# modemIO_v1.net
KiCad netlist of a schematic drawn in EAGLE
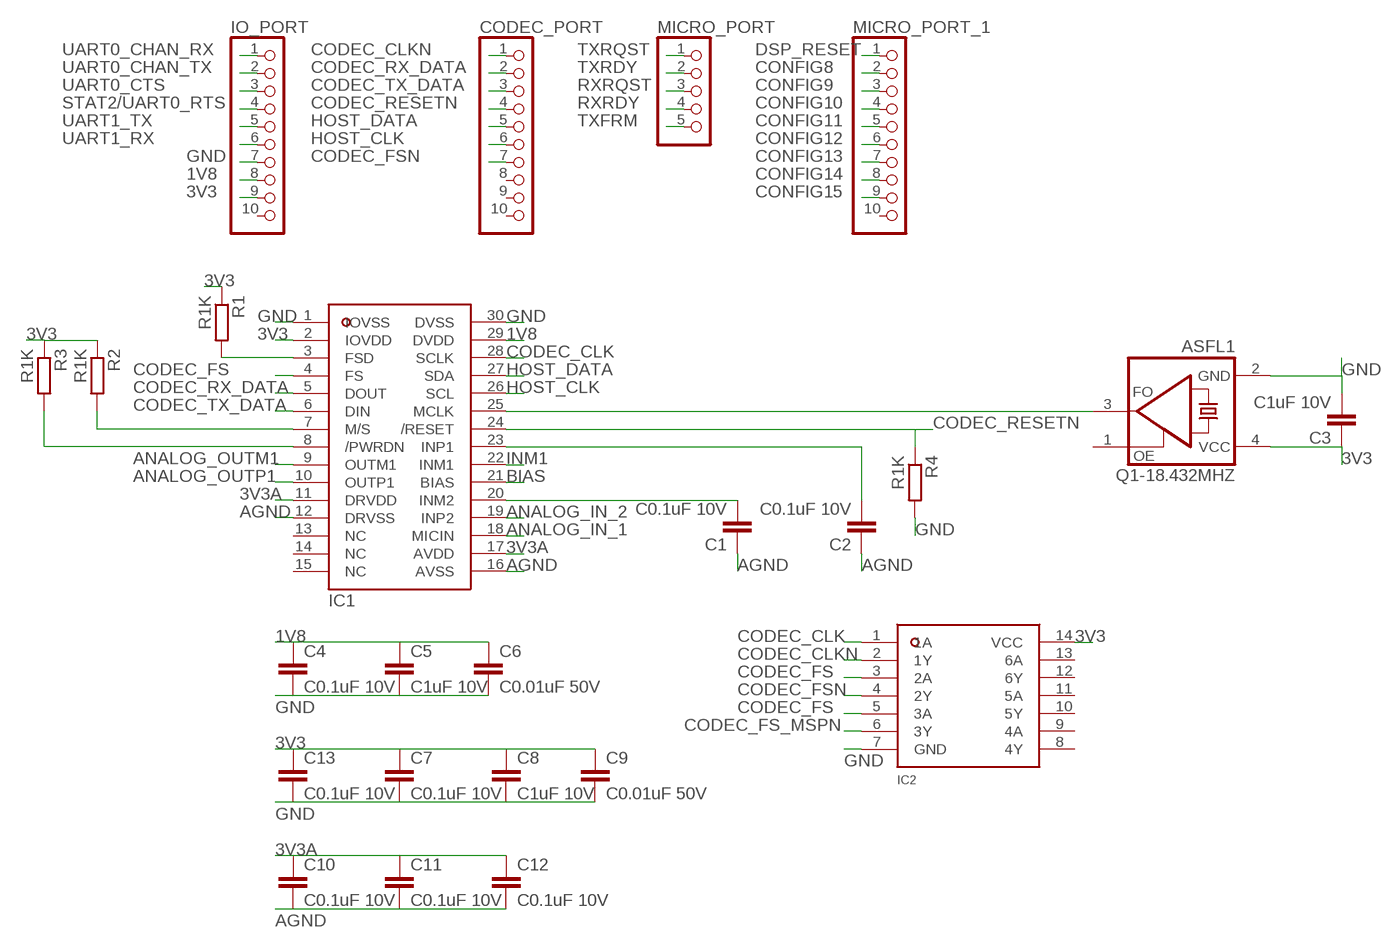
[diagram p0: schematic, sheet 1]

(export (version "E")
  (design (tool "Eeschema 10.0.6"))
  (components
    (comp (ref "C1")
      (value "C0.1uF 10V")
      (footprint "eagle-import:C0805")
      (libsource (lib "eagle-import") (part "C-EUC0805"))
    )
    (comp (ref "C2")
      (value "C0.1uF 10V")
      (footprint "eagle-import:C0805")
      (libsource (lib "eagle-import") (part "C-EUC0805"))
    )
    (comp (ref "C3")
      (value "C1uF 10V")
      (footprint "eagle-import:C0805")
      (libsource (lib "eagle-import") (part "C-EUC0805"))
    )
    (comp (ref "C4")
      (value "C0.1uF 10V")
      (footprint "eagle-import:C0805")
      (libsource (lib "eagle-import") (part "C-EUC0805"))
    )
    (comp (ref "C5")
      (value "C1uF 10V")
      (footprint "eagle-import:C0805")
      (libsource (lib "eagle-import") (part "C-EUC0805"))
    )
    (comp (ref "C6")
      (value "C0.01uF 50V")
      (footprint "eagle-import:C0805")
      (libsource (lib "eagle-import") (part "C-EUC0805"))
    )
    (comp (ref "C7")
      (value "C0.1uF 10V")
      (footprint "eagle-import:C0805")
      (libsource (lib "eagle-import") (part "C-EUC0805"))
    )
    (comp (ref "C8")
      (value "C1uF 10V")
      (footprint "eagle-import:C0805")
      (libsource (lib "eagle-import") (part "C-EUC0805"))
    )
    (comp (ref "C9")
      (value "C0.01uF 50V")
      (footprint "eagle-import:C0805")
      (libsource (lib "eagle-import") (part "C-EUC0805"))
    )
    (comp (ref "C10")
      (value "C0.1uF 10V")
      (footprint "eagle-import:C0805")
      (libsource (lib "eagle-import") (part "C-EUC0805"))
    )
    (comp (ref "C11")
      (value "C0.1uF 10V")
      (footprint "eagle-import:C0805")
      (libsource (lib "eagle-import") (part "C-EUC0805"))
    )
    (comp (ref "C12")
      (value "C0.1uF 10V")
      (footprint "eagle-import:C0805")
      (libsource (lib "eagle-import") (part "C-EUC0805"))
    )
    (comp (ref "C13")
      (value "C0.1uF 10V")
      (footprint "eagle-import:C0805")
      (libsource (lib "eagle-import") (part "C-EUC0805"))
    )
    (comp (ref "CODEC_PORT")
      (value "PINHD-1X10")
      (footprint "eagle-import:1X10")
      (libsource (lib "eagle-import") (part "PINHD-1X10"))
    )
    (comp (ref "IC1")
      (value "TLV320AIC14R-PDSO-G30")
      (footprint "eagle-import:R-PDSO-G30")
      (libsource (lib "eagle-import") (part "TLV320AIC14R-PDSO-G30"))
    )
    (comp (ref "IC2")
      (value "SN74LVC04ADRR-PDSO-G14")
      (footprint "eagle-import:R-PDSO-G14")
      (libsource (lib "eagle-import") (part "SN74LVC04ADRR-PDSO-G14"))
    )
    (comp (ref "IO_PORT")
      (value "PINHD-1X10")
      (footprint "eagle-import:1X10")
      (libsource (lib "eagle-import") (part "PINHD-1X10"))
    )
    (comp (ref "MICRO_PORT")
      (value "PINHD-1X5")
      (footprint "eagle-import:1X05")
      (libsource (lib "eagle-import") (part "PINHD-1X5"))
    )
    (comp (ref "MICRO_PORT_1")
      (value "PINHD-1X10")
      (footprint "eagle-import:1X10")
      (libsource (lib "eagle-import") (part "PINHD-1X10"))
    )
    (comp (ref "Q1-18.432MHZ")
      (value "ASFL1")
      (footprint "eagle-import:ASF")
      (fields (field (name "MF") "Abracon Corporation") (field (name "MPN") "ASFL1-125.000MHZ-EC-T"))
      (libsource (lib "eagle-import") (part "ASFL1"))
    )
    (comp (ref "R1")
      (value "R1K")
      (footprint "eagle-import:R0805")
      (libsource (lib "eagle-import") (part "R-EU_R0805"))
    )
    (comp (ref "R2")
      (value "R1K")
      (footprint "eagle-import:R0805")
      (libsource (lib "eagle-import") (part "R-EU_R0805"))
    )
    (comp (ref "R3")
      (value "R1K")
      (footprint "eagle-import:R0805")
      (libsource (lib "eagle-import") (part "R-EU_R0805"))
    )
    (comp (ref "R4")
      (value "R1K")
      (footprint "eagle-import:R0805")
      (libsource (lib "eagle-import") (part "R-EU_R0805"))
    )
  )
  (nets
    (net (code "1") (name "/1V8") (class "Default")
      (node (ref "C4") (pin "1") (pinfunction "1_1") (pintype "passive"))
      (node (ref "C5") (pin "1") (pinfunction "1_1") (pintype "passive"))
      (node (ref "C6") (pin "1") (pinfunction "1_1") (pintype "passive"))
      (node (ref "IC1") (pin "29") (pinfunction "DVDD_29") (pintype "bidirectional"))
      (node (ref "IO_PORT") (pin "8") (pinfunction "8_8") (pintype "passive"))
    )
    (net (code "2") (name "/3V3") (class "Default")
      (node (ref "C13") (pin "1") (pinfunction "1_1") (pintype "passive"))
      (node (ref "C3") (pin "1") (pinfunction "1_1") (pintype "passive"))
      (node (ref "C7") (pin "1") (pinfunction "1_1") (pintype "passive"))
      (node (ref "C8") (pin "1") (pinfunction "1_1") (pintype "passive"))
      (node (ref "C9") (pin "1") (pinfunction "1_1") (pintype "passive"))
      (node (ref "IC1") (pin "2") (pinfunction "IOVDD_2") (pintype "bidirectional"))
      (node (ref "IC2") (pin "14") (pinfunction "VCC_14") (pintype "bidirectional"))
      (node (ref "IO_PORT") (pin "9") (pinfunction "9_9") (pintype "passive"))
      (node (ref "Q1-18.432MHZ") (pin "4") (pinfunction "VCC_4") (pintype "power_in"))
      (node (ref "R1") (pin "1") (pinfunction "1_1") (pintype "passive"))
      (node (ref "R2") (pin "1") (pinfunction "1_1") (pintype "passive"))
      (node (ref "R3") (pin "1") (pinfunction "1_1") (pintype "passive"))
    )
    (net (code "3") (name "/3V3A") (class "Default")
      (node (ref "C10") (pin "1") (pinfunction "1_1") (pintype "passive"))
      (node (ref "C11") (pin "1") (pinfunction "1_1") (pintype "passive"))
      (node (ref "C12") (pin "1") (pinfunction "1_1") (pintype "passive"))
      (node (ref "IC1") (pin "11") (pinfunction "DRVDD_11") (pintype "bidirectional"))
      (node (ref "IC1") (pin "17") (pinfunction "AVDD_17") (pintype "bidirectional"))
    )
    (net (code "4") (name "/AGND") (class "Default")
      (node (ref "C1") (pin "1") (pinfunction "1_1") (pintype "passive"))
      (node (ref "C10") (pin "2") (pinfunction "2_2") (pintype "passive"))
      (node (ref "C11") (pin "2") (pinfunction "2_2") (pintype "passive"))
      (node (ref "C12") (pin "2") (pinfunction "2_2") (pintype "passive"))
      (node (ref "C2") (pin "1") (pinfunction "1_1") (pintype "passive"))
      (node (ref "IC1") (pin "12") (pinfunction "DRVSS_12") (pintype "bidirectional"))
      (node (ref "IC1") (pin "16") (pinfunction "AVSS_16") (pintype "bidirectional"))
    )
    (net (code "5") (name "/ANALOG_IN_1") (class "Default")
      (node (ref "IC1") (pin "18") (pinfunction "MICIN_18") (pintype "bidirectional"))
    )
    (net (code "6") (name "/ANALOG_IN_2") (class "Default")
      (node (ref "IC1") (pin "19") (pinfunction "INP2_19") (pintype "bidirectional"))
    )
    (net (code "7") (name "/ANALOG_OUTM1") (class "Default")
      (node (ref "IC1") (pin "9") (pinfunction "OUTM1_9") (pintype "bidirectional"))
    )
    (net (code "8") (name "/ANALOG_OUTP1") (class "Default")
      (node (ref "IC1") (pin "10") (pinfunction "OUTP1_10") (pintype "bidirectional"))
    )
    (net (code "9") (name "/BIAS") (class "Default")
      (node (ref "IC1") (pin "21") (pinfunction "BIAS_21") (pintype "bidirectional"))
    )
    (net (code "10") (name "/CODEC_CLK") (class "Default")
      (node (ref "IC1") (pin "28") (pinfunction "SCLK_28") (pintype "bidirectional"))
      (node (ref "IC2") (pin "1") (pinfunction "1A_1") (pintype "bidirectional"))
    )
    (net (code "11") (name "/CODEC_CLKN") (class "Default")
      (node (ref "CODEC_PORT") (pin "1") (pinfunction "1_1") (pintype "passive"))
      (node (ref "IC2") (pin "2") (pinfunction "1Y_2") (pintype "bidirectional"))
    )
    (net (code "12") (name "/CODEC_FS") (class "Default")
      (node (ref "IC1") (pin "4") (pinfunction "FS_4") (pintype "bidirectional"))
      (node (ref "IC2") (pin "3") (pinfunction "2A_3") (pintype "bidirectional"))
      (node (ref "IC2") (pin "5") (pinfunction "3A_5") (pintype "bidirectional"))
    )
    (net (code "13") (name "/CODEC_FSN") (class "Default")
      (node (ref "CODEC_PORT") (pin "7") (pinfunction "7_7") (pintype "passive"))
      (node (ref "IC2") (pin "4") (pinfunction "2Y_4") (pintype "bidirectional"))
    )
    (net (code "14") (name "/CODEC_FS_MSPN") (class "Default")
      (node (ref "IC2") (pin "6") (pinfunction "3Y_6") (pintype "bidirectional"))
    )
    (net (code "15") (name "/CODEC_RESETN") (class "Default")
      (node (ref "CODEC_PORT") (pin "4") (pinfunction "4_4") (pintype "passive"))
      (node (ref "IC1") (pin "24") (pinfunction "/RESET_24") (pintype "bidirectional"))
      (node (ref "R4") (pin "1") (pinfunction "1_1") (pintype "passive"))
    )
    (net (code "16") (name "/CODEC_RX_DATA") (class "Default")
      (node (ref "CODEC_PORT") (pin "2") (pinfunction "2_2") (pintype "passive"))
      (node (ref "IC1") (pin "5") (pinfunction "DOUT_5") (pintype "bidirectional"))
    )
    (net (code "17") (name "/CODEC_TX_DATA") (class "Default")
      (node (ref "CODEC_PORT") (pin "3") (pinfunction "3_3") (pintype "passive"))
      (node (ref "IC1") (pin "6") (pinfunction "DIN_6") (pintype "bidirectional"))
    )
    (net (code "18") (name "/CONFIG8") (class "Default")
      (node (ref "MICRO_PORT_1") (pin "2") (pinfunction "2_2") (pintype "passive"))
    )
    (net (code "19") (name "/CONFIG9") (class "Default")
      (node (ref "MICRO_PORT_1") (pin "3") (pinfunction "3_3") (pintype "passive"))
    )
    (net (code "20") (name "/CONFIG10") (class "Default")
      (node (ref "MICRO_PORT_1") (pin "4") (pinfunction "4_4") (pintype "passive"))
    )
    (net (code "21") (name "/CONFIG11") (class "Default")
      (node (ref "MICRO_PORT_1") (pin "5") (pinfunction "5_5") (pintype "passive"))
    )
    (net (code "22") (name "/CONFIG12") (class "Default")
      (node (ref "MICRO_PORT_1") (pin "6") (pinfunction "6_6") (pintype "passive"))
    )
    (net (code "23") (name "/CONFIG13") (class "Default")
      (node (ref "MICRO_PORT_1") (pin "7") (pinfunction "7_7") (pintype "passive"))
    )
    (net (code "24") (name "/CONFIG14") (class "Default")
      (node (ref "MICRO_PORT_1") (pin "8") (pinfunction "8_8") (pintype "passive"))
    )
    (net (code "25") (name "/CONFIG15") (class "Default")
      (node (ref "MICRO_PORT_1") (pin "9") (pinfunction "9_9") (pintype "passive"))
    )
    (net (code "26") (name "/DSP_RESET") (class "Default")
      (node (ref "MICRO_PORT_1") (pin "1") (pinfunction "1_1") (pintype "passive"))
    )
    (net (code "27") (name "/GND") (class "Default")
      (node (ref "C13") (pin "2") (pinfunction "2_2") (pintype "passive"))
      (node (ref "C3") (pin "2") (pinfunction "2_2") (pintype "passive"))
      (node (ref "C5") (pin "2") (pinfunction "2_2") (pintype "passive"))
      (node (ref "C6") (pin "2") (pinfunction "2_2") (pintype "passive"))
      (node (ref "C7") (pin "2") (pinfunction "2_2") (pintype "passive"))
      (node (ref "C8") (pin "2") (pinfunction "2_2") (pintype "passive"))
      (node (ref "C9") (pin "2") (pinfunction "2_2") (pintype "passive"))
      (node (ref "IC1") (pin "1") (pinfunction "IOVSS_1") (pintype "bidirectional"))
      (node (ref "IC1") (pin "30") (pinfunction "DVSS_30") (pintype "bidirectional"))
      (node (ref "IC2") (pin "7") (pinfunction "GND_7") (pintype "bidirectional"))
      (node (ref "IO_PORT") (pin "7") (pinfunction "7_7") (pintype "passive"))
      (node (ref "Q1-18.432MHZ") (pin "2") (pinfunction "GND_2") (pintype "power_in"))
      (node (ref "R4") (pin "2") (pinfunction "2_2") (pintype "passive"))
    )
    (net (code "28") (name "/HOST_CLK") (class "Default")
      (node (ref "CODEC_PORT") (pin "6") (pinfunction "6_6") (pintype "passive"))
      (node (ref "IC1") (pin "26") (pinfunction "SCL_26") (pintype "bidirectional"))
    )
    (net (code "29") (name "/HOST_DATA") (class "Default")
      (node (ref "CODEC_PORT") (pin "5") (pinfunction "5_5") (pintype "passive"))
      (node (ref "IC1") (pin "27") (pinfunction "SDA_27") (pintype "bidirectional"))
    )
    (net (code "30") (name "/INM1") (class "Default")
      (node (ref "IC1") (pin "22") (pinfunction "INM1_22") (pintype "bidirectional"))
    )
    (net (code "31") (name "/RXRDY") (class "Default")
      (node (ref "MICRO_PORT") (pin "4") (pinfunction "4_4") (pintype "passive"))
    )
    (net (code "32") (name "/RXRQST") (class "Default")
      (node (ref "MICRO_PORT") (pin "3") (pinfunction "3_3") (pintype "passive"))
    )
    (net (code "33") (name "/STAT2{slash}UART0_RTS") (class "Default")
      (node (ref "IO_PORT") (pin "4") (pinfunction "4_4") (pintype "passive"))
    )
    (net (code "34") (name "/TXFRM") (class "Default")
      (node (ref "MICRO_PORT") (pin "5") (pinfunction "5_5") (pintype "passive"))
    )
    (net (code "35") (name "/TXRDY") (class "Default")
      (node (ref "MICRO_PORT") (pin "2") (pinfunction "2_2") (pintype "passive"))
    )
    (net (code "36") (name "/TXRQST") (class "Default")
      (node (ref "MICRO_PORT") (pin "1") (pinfunction "1_1") (pintype "passive"))
    )
    (net (code "37") (name "/UART0_CHAN_RX") (class "Default")
      (node (ref "IO_PORT") (pin "1") (pinfunction "1_1") (pintype "passive"))
    )
    (net (code "38") (name "/UART0_CHAN_TX") (class "Default")
      (node (ref "IO_PORT") (pin "2") (pinfunction "2_2") (pintype "passive"))
    )
    (net (code "39") (name "/UART0_CTS") (class "Default")
      (node (ref "IO_PORT") (pin "3") (pinfunction "3_3") (pintype "passive"))
    )
    (net (code "40") (name "/UART1_RX") (class "Default")
      (node (ref "IO_PORT") (pin "6") (pinfunction "6_6") (pintype "passive"))
    )
    (net (code "41") (name "/UART1_TX") (class "Default")
      (node (ref "IO_PORT") (pin "5") (pinfunction "5_5") (pintype "passive"))
    )
    (net (code "42") (name "Net-(IC1-FSD)") (class "Default")
      (node (ref "IC1") (pin "3") (pinfunction "FSD_3") (pintype "bidirectional"))
      (node (ref "R1") (pin "2") (pinfunction "2_2") (pintype "passive"))
    )
    (net (code "43") (name "Net-(IC1-INM2)") (class "Default")
      (node (ref "C1") (pin "2") (pinfunction "2_2") (pintype "passive"))
      (node (ref "IC1") (pin "20") (pinfunction "INM2_20") (pintype "bidirectional"))
    )
    (net (code "44") (name "Net-(IC1-INP1)") (class "Default")
      (node (ref "C2") (pin "2") (pinfunction "2_2") (pintype "passive"))
      (node (ref "IC1") (pin "23") (pinfunction "INP1_23") (pintype "bidirectional"))
    )
    (net (code "45") (name "Net-(IC1-MCLK)") (class "Default")
      (node (ref "IC1") (pin "25") (pinfunction "MCLK_25") (pintype "bidirectional"))
      (node (ref "Q1-18.432MHZ") (pin "3") (pinfunction "FO_3") (pintype "output"))
    )
    (net (code "46") (name "Net-(IC1-M{slash}S)") (class "Default")
      (node (ref "IC1") (pin "7") (pinfunction "M/S_7") (pintype "bidirectional"))
      (node (ref "R2") (pin "2") (pinfunction "2_2") (pintype "passive"))
    )
    (net (code "47") (name "Net-(IC1-{slash}PWRDN)") (class "Default")
      (node (ref "IC1") (pin "8") (pinfunction "/PWRDN_8") (pintype "bidirectional"))
      (node (ref "R3") (pin "2") (pinfunction "2_2") (pintype "passive"))
    )
    (net (code "48") (name "unconnected-(C4-Pad2)") (class "Default")
      (node (ref "C4") (pin "2") (pinfunction "2_2") (pintype "passive"))
    )
    (net (code "49") (name "unconnected-(CODEC_PORT-Pad8)") (class "Default")
      (node (ref "CODEC_PORT") (pin "8") (pinfunction "8_8") (pintype "passive"))
    )
    (net (code "50") (name "unconnected-(CODEC_PORT-Pad9)") (class "Default")
      (node (ref "CODEC_PORT") (pin "9") (pinfunction "9_9") (pintype "passive"))
    )
    (net (code "51") (name "unconnected-(CODEC_PORT-Pad10)") (class "Default")
      (node (ref "CODEC_PORT") (pin "10") (pinfunction "10_10") (pintype "passive"))
    )
    (net (code "52") (name "unconnected-(IC1-NC-Pad13)") (class "Default")
      (node (ref "IC1") (pin "13") (pinfunction "NC_13") (pintype "bidirectional"))
    )
    (net (code "53") (name "unconnected-(IC1-NC-Pad14)") (class "Default")
      (node (ref "IC1") (pin "14") (pinfunction "NC_14") (pintype "bidirectional"))
    )
    (net (code "54") (name "unconnected-(IC1-NC-Pad15)") (class "Default")
      (node (ref "IC1") (pin "15") (pinfunction "NC_15") (pintype "bidirectional"))
    )
    (net (code "55") (name "unconnected-(IC2-4A-Pad9)") (class "Default")
      (node (ref "IC2") (pin "9") (pinfunction "4A_9") (pintype "bidirectional"))
    )
    (net (code "56") (name "unconnected-(IC2-4Y-Pad8)") (class "Default")
      (node (ref "IC2") (pin "8") (pinfunction "4Y_8") (pintype "bidirectional"))
    )
    (net (code "57") (name "unconnected-(IC2-5A-Pad11)") (class "Default")
      (node (ref "IC2") (pin "11") (pinfunction "5A_11") (pintype "bidirectional"))
    )
    (net (code "58") (name "unconnected-(IC2-5Y-Pad10)") (class "Default")
      (node (ref "IC2") (pin "10") (pinfunction "5Y_10") (pintype "bidirectional"))
    )
    (net (code "59") (name "unconnected-(IC2-6A-Pad13)") (class "Default")
      (node (ref "IC2") (pin "13") (pinfunction "6A_13") (pintype "bidirectional"))
    )
    (net (code "60") (name "unconnected-(IC2-6Y-Pad12)") (class "Default")
      (node (ref "IC2") (pin "12") (pinfunction "6Y_12") (pintype "bidirectional"))
    )
    (net (code "61") (name "unconnected-(IO_PORT-Pad10)") (class "Default")
      (node (ref "IO_PORT") (pin "10") (pinfunction "10_10") (pintype "passive"))
    )
    (net (code "62") (name "unconnected-(MICRO_PORT_1-Pad10)") (class "Default")
      (node (ref "MICRO_PORT_1") (pin "10") (pinfunction "10_10") (pintype "passive"))
    )
    (net (code "63") (name "unconnected-(Q1-18.432MHZ-OE-Pad1)") (class "Default")
      (node (ref "Q1-18.432MHZ") (pin "1") (pinfunction "OE_1") (pintype "input"))
    )
  )
)
